# altium.net
KiCad netlist of a schematic drawn in Altium Designer
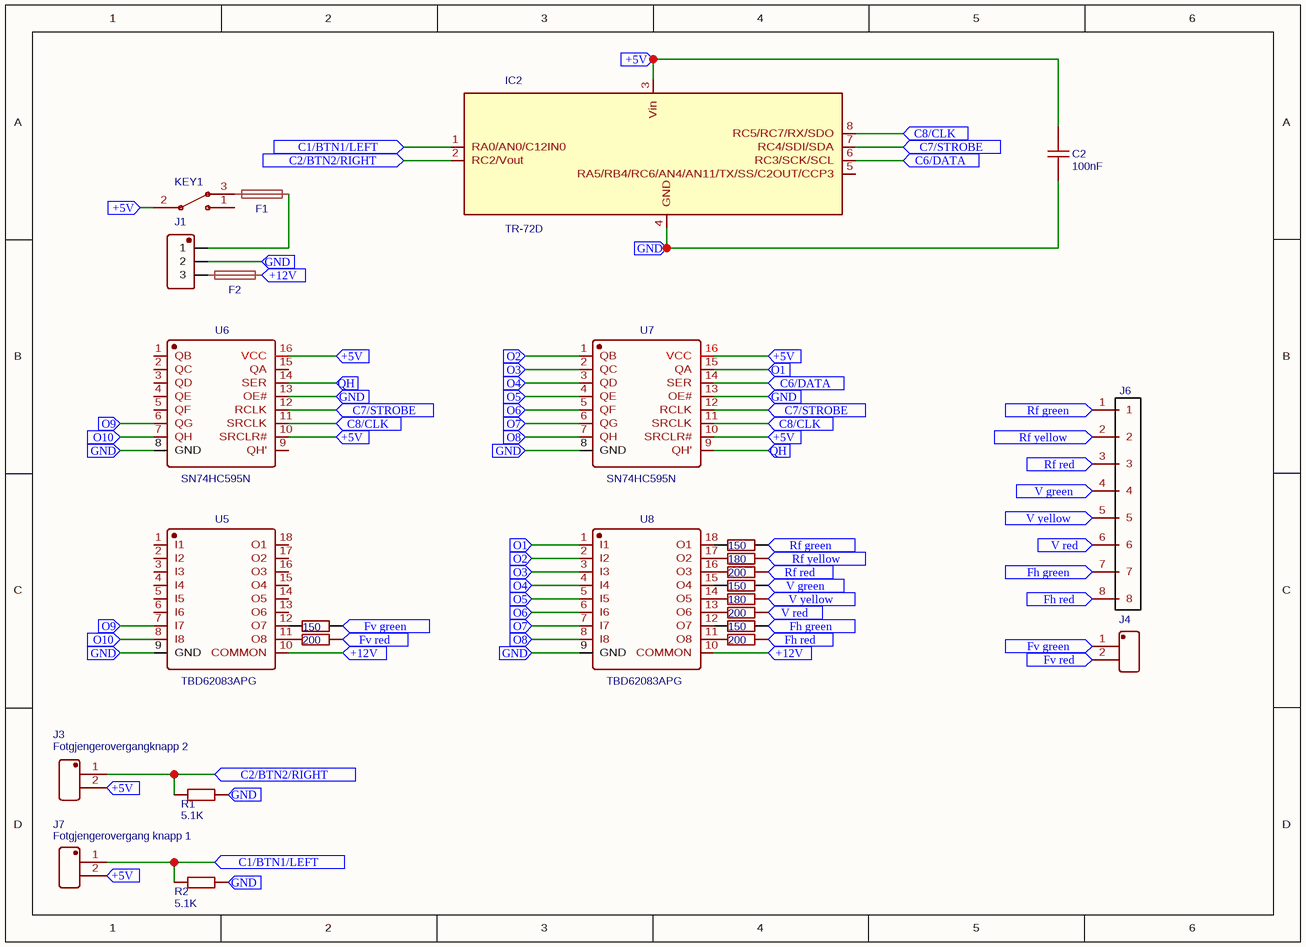
[diagram p0: altium.schdoc]

(export (version "E")
  (design (tool "Eeschema 10.0.6"))
  (components
    (comp (ref "C2")
      (value "100nF")
      (fields
        (field (name "BOM_SUPPLIER PART") "C304011")
        (field (name "BOM_MANUFACTURER PART") "1210B106K100CT")
        (field (name "CONTRIBUTOR") "LCSC")
      )
      (libsource (lib "altium-import") (part "root_3_100nF_"))
    )
    (comp (ref "F1")
      (value "NO")
      (fields
        (field (name "BOM_MANUFACTURER PART") "3403.0015.11")
        (field (name "BOM_SUPPLIER PART") "693-3403.0015.11")
        (field (name "CONTRIBUTOR") "romiksm")
      )
      (libsource (lib "altium-import") (part "root_0_NO_"))
    )
    (comp (ref "F2")
      (value "NO")
      (fields
        (field (name "BOM_MANUFACTURER PART") "3403.0015.11")
        (field (name "BOM_SUPPLIER PART") "693-3403.0015.11")
        (field (name "CONTRIBUTOR") "romiksm")
      )
      (libsource (lib "altium-import") (part "root_0_NO_"))
    )
    (comp (ref "IC2")
      (value "TR-72D")
      (fields (field (name "CONTRIBUTOR") "Simen Stensas"))
      (libsource (lib "altium-import") (part "root_0_TR-72D_"))
    )
    (comp (ref "J1")
      (value "KF127_3P_5.08")
      (fields (field (name "CONTRIBUTOR") "GrahamG"))
      (libsource (lib "altium-import") (part "root_0_KF127_3P_5.08_"))
    )
    (comp (ref "J3")
      (value "Fotgjengerovergangknapp 2")
      (fields (field (name "BOM_MANUFACTURER PART") "KF127L-5.08") (field (name "CONTRIBUTOR") "GrahamG"))
      (libsource (lib "altium-import") (part "root_0_Fotgjengerovergangknapp 2_"))
    )
    (comp (ref "J4")
      (value "KF127_2P_5.08")
      (fields (field (name "BOM_MANUFACTURER PART") "KF127L-5.08") (field (name "CONTRIBUTOR") "GrahamG"))
      (libsource (lib "altium-import") (part "root_0_KF127_2P_5.08_"))
    )
    (comp (ref "J6")
      (value "KF127-8P")
      (fields (field (name "CONTRIBUTOR") "milton.sanchez.alban"))
      (libsource (lib "altium-import") (part "root_0_KF127-8P_"))
    )
    (comp (ref "J7")
      (value "Fotgjengerovergang knapp 1")
      (fields (field (name "BOM_MANUFACTURER PART") "KF127L-5.08") (field (name "CONTRIBUTOR") "GrahamG"))
      (libsource (lib "altium-import") (part "root_0_Fotgjengerovergang knapp 1_"))
    )
    (comp (ref "KEY1")
      (value "MSK-11027 Toggle Switches")
      (fields (field (name "BOM_SUPPLIER PART") "C21381"))
      (libsource (lib "altium-import") (part "root_0_MSK-11027 Toggle Switches_"))
    )
    (comp (ref "R1")
      (value "5.1K")
      (fields
        (field (name "BOM_SUPPLIER PART") "C325932")
        (field (name "BOM_MANUFACTURER PART") "RMC12065.1K1%N")
        (field (name "CONTRIBUTOR") "LCSC")
      )
      (libsource (lib "altium-import") (part "root_0_5.1K_"))
    )
    (comp (ref "R2")
      (value "5.1K")
      (fields
        (field (name "BOM_SUPPLIER PART") "C325932")
        (field (name "BOM_MANUFACTURER PART") "RMC12065.1K1%N")
        (field (name "CONTRIBUTOR") "LCSC")
      )
      (libsource (lib "altium-import") (part "root_0_5.1K_"))
    )
    (comp (ref "R3")
      (value "150")
      (fields
        (field (name "BOM_MANUFACTURER PART") "RC1206JR-07160RL")
        (field (name "BOM_SUPPLIER PART") "C137196")
      )
      (libsource (lib "altium-import") (part "root_0_150_"))
    )
    (comp (ref "R4")
      (value "200")
      (fields
        (field (name "BOM_MANUFACTURER PART") "QR1206J200RP05")
        (field (name "BOM_SUPPLIER PART") "C149886")
        (field (name "CONTRIBUTOR") "LCSC")
      )
      (libsource (lib "altium-import") (part "root_0_200_"))
    )
    (comp (ref "R5")
      (value "200")
      (fields
        (field (name "BOM_MANUFACTURER PART") "QR1206J200RP05")
        (field (name "BOM_SUPPLIER PART") "C149886")
        (field (name "CONTRIBUTOR") "LCSC")
      )
      (libsource (lib "altium-import") (part "root_0_200_"))
    )
    (comp (ref "R6")
      (value "200")
      (fields
        (field (name "BOM_MANUFACTURER PART") "QR1206J200RP05")
        (field (name "BOM_SUPPLIER PART") "C149886")
        (field (name "CONTRIBUTOR") "LCSC")
      )
      (libsource (lib "altium-import") (part "root_0_200_"))
    )
    (comp (ref "R7")
      (value "200")
      (fields
        (field (name "BOM_MANUFACTURER PART") "QR1206J200RP05")
        (field (name "BOM_SUPPLIER PART") "C149886")
        (field (name "CONTRIBUTOR") "LCSC")
      )
      (libsource (lib "altium-import") (part "root_0_200_"))
    )
    (comp (ref "R16")
      (value "180")
      (fields
        (field (name "BOM_SUPPLIER PART") "C204708")
        (field (name "BOM_MANUFACTURER PART") "CR1206-FX-1800ELF")
        (field (name "CONTRIBUTOR") "LCSC")
      )
      (libsource (lib "altium-import") (part "root_0_180_"))
    )
    (comp (ref "R17")
      (value "180")
      (fields
        (field (name "BOM_SUPPLIER PART") "C204708")
        (field (name "BOM_MANUFACTURER PART") "CR1206-FX-1800ELF")
        (field (name "CONTRIBUTOR") "LCSC")
      )
      (libsource (lib "altium-import") (part "root_0_180_"))
    )
    (comp (ref "R18")
      (value "150")
      (fields
        (field (name "BOM_MANUFACTURER PART") "RC1206JR-07160RL")
        (field (name "BOM_SUPPLIER PART") "C137196")
      )
      (libsource (lib "altium-import") (part "root_0_150_"))
    )
    (comp (ref "R19")
      (value "150")
      (fields
        (field (name "BOM_MANUFACTURER PART") "RC1206JR-07160RL")
        (field (name "BOM_SUPPLIER PART") "C137196")
      )
      (libsource (lib "altium-import") (part "root_0_150_"))
    )
    (comp (ref "R20")
      (value "150")
      (fields
        (field (name "BOM_MANUFACTURER PART") "RC1206JR-07160RL")
        (field (name "BOM_SUPPLIER PART") "C137196")
      )
      (libsource (lib "altium-import") (part "root_0_150_"))
    )
    (comp (ref "U5")
      (value "TBD62083APG")
      (fields (field (name "BOM_SUPPLIER PART") "C114143") (field (name "CONTRIBUTOR") "LCSC"))
      (libsource (lib "altium-import") (part "root_0_TBD62083APG_"))
    )
    (comp (ref "U6")
      (value "SN74HC595N")
      (fields (field (name "BOM_SUPPLIER PART") "C78711"))
      (libsource (lib "altium-import") (part "root_0_SN74HC595N_"))
    )
    (comp (ref "U7")
      (value "SN74HC595N")
      (fields (field (name "BOM_SUPPLIER PART") "C78711"))
      (libsource (lib "altium-import") (part "root_0_SN74HC595N_"))
    )
    (comp (ref "U8")
      (value "TBD62083APG")
      (fields (field (name "BOM_SUPPLIER PART") "C114143") (field (name "CONTRIBUTOR") "LCSC"))
      (libsource (lib "altium-import") (part "root_0_TBD62083APG_"))
    )
  )
  (nets
    (net (code "1") (name "/+5V") (class "Default")
      (node (ref "C2") (pin "2") (pinfunction "2_2") (pintype "passive"))
      (node (ref "IC2") (pin "3") (pinfunction "Vin_3") (pintype "passive"))
      (node (ref "J3") (pin "2") (pinfunction "PIN2_2") (pintype "passive"))
      (node (ref "J7") (pin "2") (pinfunction "PIN2_2") (pintype "passive"))
      (node (ref "KEY1") (pin "2") (pinfunction "2_2") (pintype "passive"))
      (node (ref "U6") (pin "10") (pinfunction "SRCLR#_10") (pintype "passive"))
      (node (ref "U6") (pin "16") (pinfunction "VCC_16") (pintype "passive"))
      (node (ref "U7") (pin "10") (pinfunction "SRCLR#_10") (pintype "passive"))
      (node (ref "U7") (pin "16") (pinfunction "VCC_16") (pintype "passive"))
    )
    (net (code "2") (name "/+12V") (class "Default")
      (node (ref "F2") (pin "2") (pinfunction "2_2") (pintype "passive"))
      (node (ref "U5") (pin "10") (pinfunction "COMMON_10") (pintype "passive"))
      (node (ref "U8") (pin "10") (pinfunction "COMMON_10") (pintype "passive"))
    )
    (net (code "3") (name "/C1{slash}BTN1{slash}LEFT") (class "Default")
      (node (ref "IC2") (pin "1") (pinfunction "RA0/AN0/C12IN0_1") (pintype "passive"))
      (node (ref "J7") (pin "1") (pinfunction "PIN1_1") (pintype "passive"))
      (node (ref "R2") (pin "1") (pinfunction "1_1") (pintype "passive"))
    )
    (net (code "4") (name "/C2{slash}BTN2{slash}RIGHT") (class "Default")
      (node (ref "IC2") (pin "2") (pinfunction "RC2/Vout_2") (pintype "passive"))
      (node (ref "J3") (pin "1") (pinfunction "PIN1_1") (pintype "passive"))
      (node (ref "R1") (pin "1") (pinfunction "1_1") (pintype "passive"))
    )
    (net (code "5") (name "/C6{slash}DATA") (class "Default")
      (node (ref "IC2") (pin "6") (pinfunction "RC3/SCK/SCL_6") (pintype "passive"))
      (node (ref "U7") (pin "14") (pinfunction "SER_14") (pintype "passive"))
    )
    (net (code "6") (name "/C7{slash}STROBE") (class "Default")
      (node (ref "IC2") (pin "7") (pinfunction "RC4/SDI/SDA_7") (pintype "passive"))
      (node (ref "U6") (pin "12") (pinfunction "RCLK_12") (pintype "passive"))
      (node (ref "U7") (pin "12") (pinfunction "RCLK_12") (pintype "passive"))
    )
    (net (code "7") (name "/C8{slash}CLK") (class "Default")
      (node (ref "IC2") (pin "8") (pinfunction "RC5/RC7/RX/SDO_8") (pintype "passive"))
      (node (ref "U6") (pin "11") (pinfunction "SRCLK_11") (pintype "passive"))
      (node (ref "U7") (pin "11") (pinfunction "SRCLK_11") (pintype "passive"))
    )
    (net (code "8") (name "/Fh green") (class "Default")
      (node (ref "J6") (pin "7") (pinfunction "7_7") (pintype "passive"))
      (node (ref "R18") (pin "2") (pinfunction "2_2") (pintype "passive"))
    )
    (net (code "9") (name "/Fh red") (class "Default")
      (node (ref "J6") (pin "8") (pinfunction "8_8") (pintype "passive"))
      (node (ref "R5") (pin "2") (pinfunction "2_2") (pintype "passive"))
    )
    (net (code "10") (name "/Fv green") (class "Default")
      (node (ref "J4") (pin "1") (pinfunction "PIN1_1") (pintype "passive"))
      (node (ref "R3") (pin "2") (pinfunction "2_2") (pintype "passive"))
    )
    (net (code "11") (name "/Fv red") (class "Default")
      (node (ref "J4") (pin "2") (pinfunction "PIN2_2") (pintype "passive"))
      (node (ref "R4") (pin "2") (pinfunction "2_2") (pintype "passive"))
    )
    (net (code "12") (name "/GND") (class "Default")
      (node (ref "C2") (pin "1") (pinfunction "1_1") (pintype "passive"))
      (node (ref "IC2") (pin "4") (pinfunction "GND_4") (pintype "passive"))
      (node (ref "J1") (pin "2") (pinfunction "2_2") (pintype "passive"))
      (node (ref "R1") (pin "2") (pinfunction "2_2") (pintype "passive"))
      (node (ref "R2") (pin "2") (pinfunction "2_2") (pintype "passive"))
      (node (ref "U5") (pin "9") (pinfunction "GND_9") (pintype "passive"))
      (node (ref "U6") (pin "13") (pinfunction "OE#_13") (pintype "passive"))
      (node (ref "U6") (pin "8") (pinfunction "GND_8") (pintype "passive"))
      (node (ref "U7") (pin "13") (pinfunction "OE#_13") (pintype "passive"))
      (node (ref "U7") (pin "8") (pinfunction "GND_8") (pintype "passive"))
      (node (ref "U8") (pin "9") (pinfunction "GND_9") (pintype "passive"))
    )
    (net (code "13") (name "/O1") (class "Default")
      (node (ref "U7") (pin "15") (pinfunction "QA_15") (pintype "passive"))
      (node (ref "U8") (pin "1") (pinfunction "I1_1") (pintype "passive"))
    )
    (net (code "14") (name "/O2") (class "Default")
      (node (ref "U7") (pin "1") (pinfunction "QB_1") (pintype "passive"))
      (node (ref "U8") (pin "2") (pinfunction "I2_2") (pintype "passive"))
    )
    (net (code "15") (name "/O3") (class "Default")
      (node (ref "U7") (pin "2") (pinfunction "QC_2") (pintype "passive"))
      (node (ref "U8") (pin "3") (pinfunction "I3_3") (pintype "passive"))
    )
    (net (code "16") (name "/O4") (class "Default")
      (node (ref "U7") (pin "3") (pinfunction "QD_3") (pintype "passive"))
      (node (ref "U8") (pin "4") (pinfunction "I4_4") (pintype "passive"))
    )
    (net (code "17") (name "/O5") (class "Default")
      (node (ref "U7") (pin "4") (pinfunction "QE_4") (pintype "passive"))
      (node (ref "U8") (pin "5") (pinfunction "I5_5") (pintype "passive"))
    )
    (net (code "18") (name "/O6") (class "Default")
      (node (ref "U7") (pin "5") (pinfunction "QF_5") (pintype "passive"))
      (node (ref "U8") (pin "6") (pinfunction "I6_6") (pintype "passive"))
    )
    (net (code "19") (name "/O7") (class "Default")
      (node (ref "U7") (pin "6") (pinfunction "QG_6") (pintype "passive"))
      (node (ref "U8") (pin "7") (pinfunction "I7_7") (pintype "passive"))
    )
    (net (code "20") (name "/O8") (class "Default")
      (node (ref "U7") (pin "7") (pinfunction "QH_7") (pintype "passive"))
      (node (ref "U8") (pin "8") (pinfunction "I8_8") (pintype "passive"))
    )
    (net (code "21") (name "/O9") (class "Default")
      (node (ref "U5") (pin "7") (pinfunction "I7_7") (pintype "passive"))
      (node (ref "U6") (pin "6") (pinfunction "QG_6") (pintype "passive"))
    )
    (net (code "22") (name "/O10") (class "Default")
      (node (ref "U5") (pin "8") (pinfunction "I8_8") (pintype "passive"))
      (node (ref "U6") (pin "7") (pinfunction "QH_7") (pintype "passive"))
    )
    (net (code "23") (name "/QH") (class "Default")
      (node (ref "U6") (pin "14") (pinfunction "SER_14") (pintype "passive"))
      (node (ref "U7") (pin "9") (pinfunction "QH'_9") (pintype "passive"))
    )
    (net (code "24") (name "/Rf green") (class "Default")
      (node (ref "J6") (pin "1") (pinfunction "1_1") (pintype "passive"))
      (node (ref "R20") (pin "2") (pinfunction "2_2") (pintype "passive"))
    )
    (net (code "25") (name "/Rf red") (class "Default")
      (node (ref "J6") (pin "3") (pinfunction "3_3") (pintype "passive"))
      (node (ref "R7") (pin "2") (pinfunction "2_2") (pintype "passive"))
    )
    (net (code "26") (name "/Rf yellow") (class "Default")
      (node (ref "J6") (pin "2") (pinfunction "2_2") (pintype "passive"))
      (node (ref "R17") (pin "2") (pinfunction "2_2") (pintype "passive"))
    )
    (net (code "27") (name "/V green") (class "Default")
      (node (ref "J6") (pin "4") (pinfunction "4_4") (pintype "passive"))
      (node (ref "R19") (pin "2") (pinfunction "2_2") (pintype "passive"))
    )
    (net (code "28") (name "/V red") (class "Default")
      (node (ref "J6") (pin "6") (pinfunction "6_6") (pintype "passive"))
      (node (ref "R6") (pin "2") (pinfunction "2_2") (pintype "passive"))
    )
    (net (code "29") (name "/V yellow") (class "Default")
      (node (ref "J6") (pin "5") (pinfunction "5_5") (pintype "passive"))
      (node (ref "R16") (pin "2") (pinfunction "2_2") (pintype "passive"))
    )
    (net (code "30") (name "Net-(F1-Pad1)") (class "Default")
      (node (ref "F1") (pin "1") (pinfunction "1_1") (pintype "passive"))
      (node (ref "KEY1") (pin "3") (pinfunction "3_3") (pintype "passive"))
    )
    (net (code "31") (name "Net-(F1-Pad2)") (class "Default")
      (node (ref "F1") (pin "2") (pinfunction "2_2") (pintype "passive"))
      (node (ref "J1") (pin "1") (pinfunction "1_1") (pintype "passive"))
    )
    (net (code "32") (name "Net-(F2-Pad1)") (class "Default")
      (node (ref "F2") (pin "1") (pinfunction "1_1") (pintype "passive"))
      (node (ref "J1") (pin "3") (pinfunction "3_3") (pintype "passive"))
    )
    (net (code "33") (name "Net-(U5-O7)") (class "Default")
      (node (ref "R3") (pin "1") (pinfunction "1_1") (pintype "passive"))
      (node (ref "U5") (pin "12") (pinfunction "O7_12") (pintype "passive"))
    )
    (net (code "34") (name "Net-(U5-O8)") (class "Default")
      (node (ref "R4") (pin "1") (pinfunction "1_1") (pintype "passive"))
      (node (ref "U5") (pin "11") (pinfunction "O8_11") (pintype "passive"))
    )
    (net (code "35") (name "Net-(U8-O1)") (class "Default")
      (node (ref "R20") (pin "1") (pinfunction "1_1") (pintype "passive"))
      (node (ref "U8") (pin "18") (pinfunction "O1_18") (pintype "passive"))
    )
    (net (code "36") (name "Net-(U8-O2)") (class "Default")
      (node (ref "R17") (pin "1") (pinfunction "1_1") (pintype "passive"))
      (node (ref "U8") (pin "17") (pinfunction "O2_17") (pintype "passive"))
    )
    (net (code "37") (name "Net-(U8-O3)") (class "Default")
      (node (ref "R7") (pin "1") (pinfunction "1_1") (pintype "passive"))
      (node (ref "U8") (pin "16") (pinfunction "O3_16") (pintype "passive"))
    )
    (net (code "38") (name "Net-(U8-O4)") (class "Default")
      (node (ref "R19") (pin "1") (pinfunction "1_1") (pintype "passive"))
      (node (ref "U8") (pin "15") (pinfunction "O4_15") (pintype "passive"))
    )
    (net (code "39") (name "Net-(U8-O5)") (class "Default")
      (node (ref "R16") (pin "1") (pinfunction "1_1") (pintype "passive"))
      (node (ref "U8") (pin "14") (pinfunction "O5_14") (pintype "passive"))
    )
    (net (code "40") (name "Net-(U8-O6)") (class "Default")
      (node (ref "R6") (pin "1") (pinfunction "1_1") (pintype "passive"))
      (node (ref "U8") (pin "13") (pinfunction "O6_13") (pintype "passive"))
    )
    (net (code "41") (name "Net-(U8-O7)") (class "Default")
      (node (ref "R18") (pin "1") (pinfunction "1_1") (pintype "passive"))
      (node (ref "U8") (pin "12") (pinfunction "O7_12") (pintype "passive"))
    )
    (net (code "42") (name "Net-(U8-O8)") (class "Default")
      (node (ref "R5") (pin "1") (pinfunction "1_1") (pintype "passive"))
      (node (ref "U8") (pin "11") (pinfunction "O8_11") (pintype "passive"))
    )
    (net (code "43") (name "unconnected-(IC2-RA5{slash}RB4{slash}RC6{slash}AN4{slash}AN11{slash}TX{slash}SS{slash}C2OUT{slash}CCP3-Pad5)") (class "Default")
      (node (ref "IC2") (pin "5") (pinfunction "RA5/RB4/RC6/AN4/AN11/TX/SS/C2OUT/CCP3_5") (pintype "passive"))
    )
    (net (code "44") (name "unconnected-(KEY1-Pad1)") (class "Default")
      (node (ref "KEY1") (pin "1") (pinfunction "1_1") (pintype "passive"))
    )
    (net (code "45") (name "unconnected-(U5-I1-Pad1)") (class "Default")
      (node (ref "U5") (pin "1") (pinfunction "I1_1") (pintype "passive"))
    )
    (net (code "46") (name "unconnected-(U5-I2-Pad2)") (class "Default")
      (node (ref "U5") (pin "2") (pinfunction "I2_2") (pintype "passive"))
    )
    (net (code "47") (name "unconnected-(U5-I3-Pad3)") (class "Default")
      (node (ref "U5") (pin "3") (pinfunction "I3_3") (pintype "passive"))
    )
    (net (code "48") (name "unconnected-(U5-I4-Pad4)") (class "Default")
      (node (ref "U5") (pin "4") (pinfunction "I4_4") (pintype "passive"))
    )
    (net (code "49") (name "unconnected-(U5-I5-Pad5)") (class "Default")
      (node (ref "U5") (pin "5") (pinfunction "I5_5") (pintype "passive"))
    )
    (net (code "50") (name "unconnected-(U5-I6-Pad6)") (class "Default")
      (node (ref "U5") (pin "6") (pinfunction "I6_6") (pintype "passive"))
    )
    (net (code "51") (name "unconnected-(U5-O1-Pad18)") (class "Default")
      (node (ref "U5") (pin "18") (pinfunction "O1_18") (pintype "passive"))
    )
    (net (code "52") (name "unconnected-(U5-O2-Pad17)") (class "Default")
      (node (ref "U5") (pin "17") (pinfunction "O2_17") (pintype "passive"))
    )
    (net (code "53") (name "unconnected-(U5-O3-Pad16)") (class "Default")
      (node (ref "U5") (pin "16") (pinfunction "O3_16") (pintype "passive"))
    )
    (net (code "54") (name "unconnected-(U5-O4-Pad15)") (class "Default")
      (node (ref "U5") (pin "15") (pinfunction "O4_15") (pintype "passive"))
    )
    (net (code "55") (name "unconnected-(U5-O5-Pad14)") (class "Default")
      (node (ref "U5") (pin "14") (pinfunction "O5_14") (pintype "passive"))
    )
    (net (code "56") (name "unconnected-(U5-O6-Pad13)") (class "Default")
      (node (ref "U5") (pin "13") (pinfunction "O6_13") (pintype "passive"))
    )
    (net (code "57") (name "unconnected-(U6-QA-Pad15)") (class "Default")
      (node (ref "U6") (pin "15") (pinfunction "QA_15") (pintype "passive"))
    )
    (net (code "58") (name "unconnected-(U6-QB-Pad1)") (class "Default")
      (node (ref "U6") (pin "1") (pinfunction "QB_1") (pintype "passive"))
    )
    (net (code "59") (name "unconnected-(U6-QC-Pad2)") (class "Default")
      (node (ref "U6") (pin "2") (pinfunction "QC_2") (pintype "passive"))
    )
    (net (code "60") (name "unconnected-(U6-QD-Pad3)") (class "Default")
      (node (ref "U6") (pin "3") (pinfunction "QD_3") (pintype "passive"))
    )
    (net (code "61") (name "unconnected-(U6-QE-Pad4)") (class "Default")
      (node (ref "U6") (pin "4") (pinfunction "QE_4") (pintype "passive"))
    )
    (net (code "62") (name "unconnected-(U6-QF-Pad5)") (class "Default")
      (node (ref "U6") (pin "5") (pinfunction "QF_5") (pintype "passive"))
    )
    (net (code "63") (name "unconnected-(U6-QH'-Pad9)") (class "Default")
      (node (ref "U6") (pin "9") (pinfunction "QH'_9") (pintype "passive"))
    )
  )
)
